# 000_Power_and_Loads.net
KiCad netlist of a schematic drawn in Altium Designer
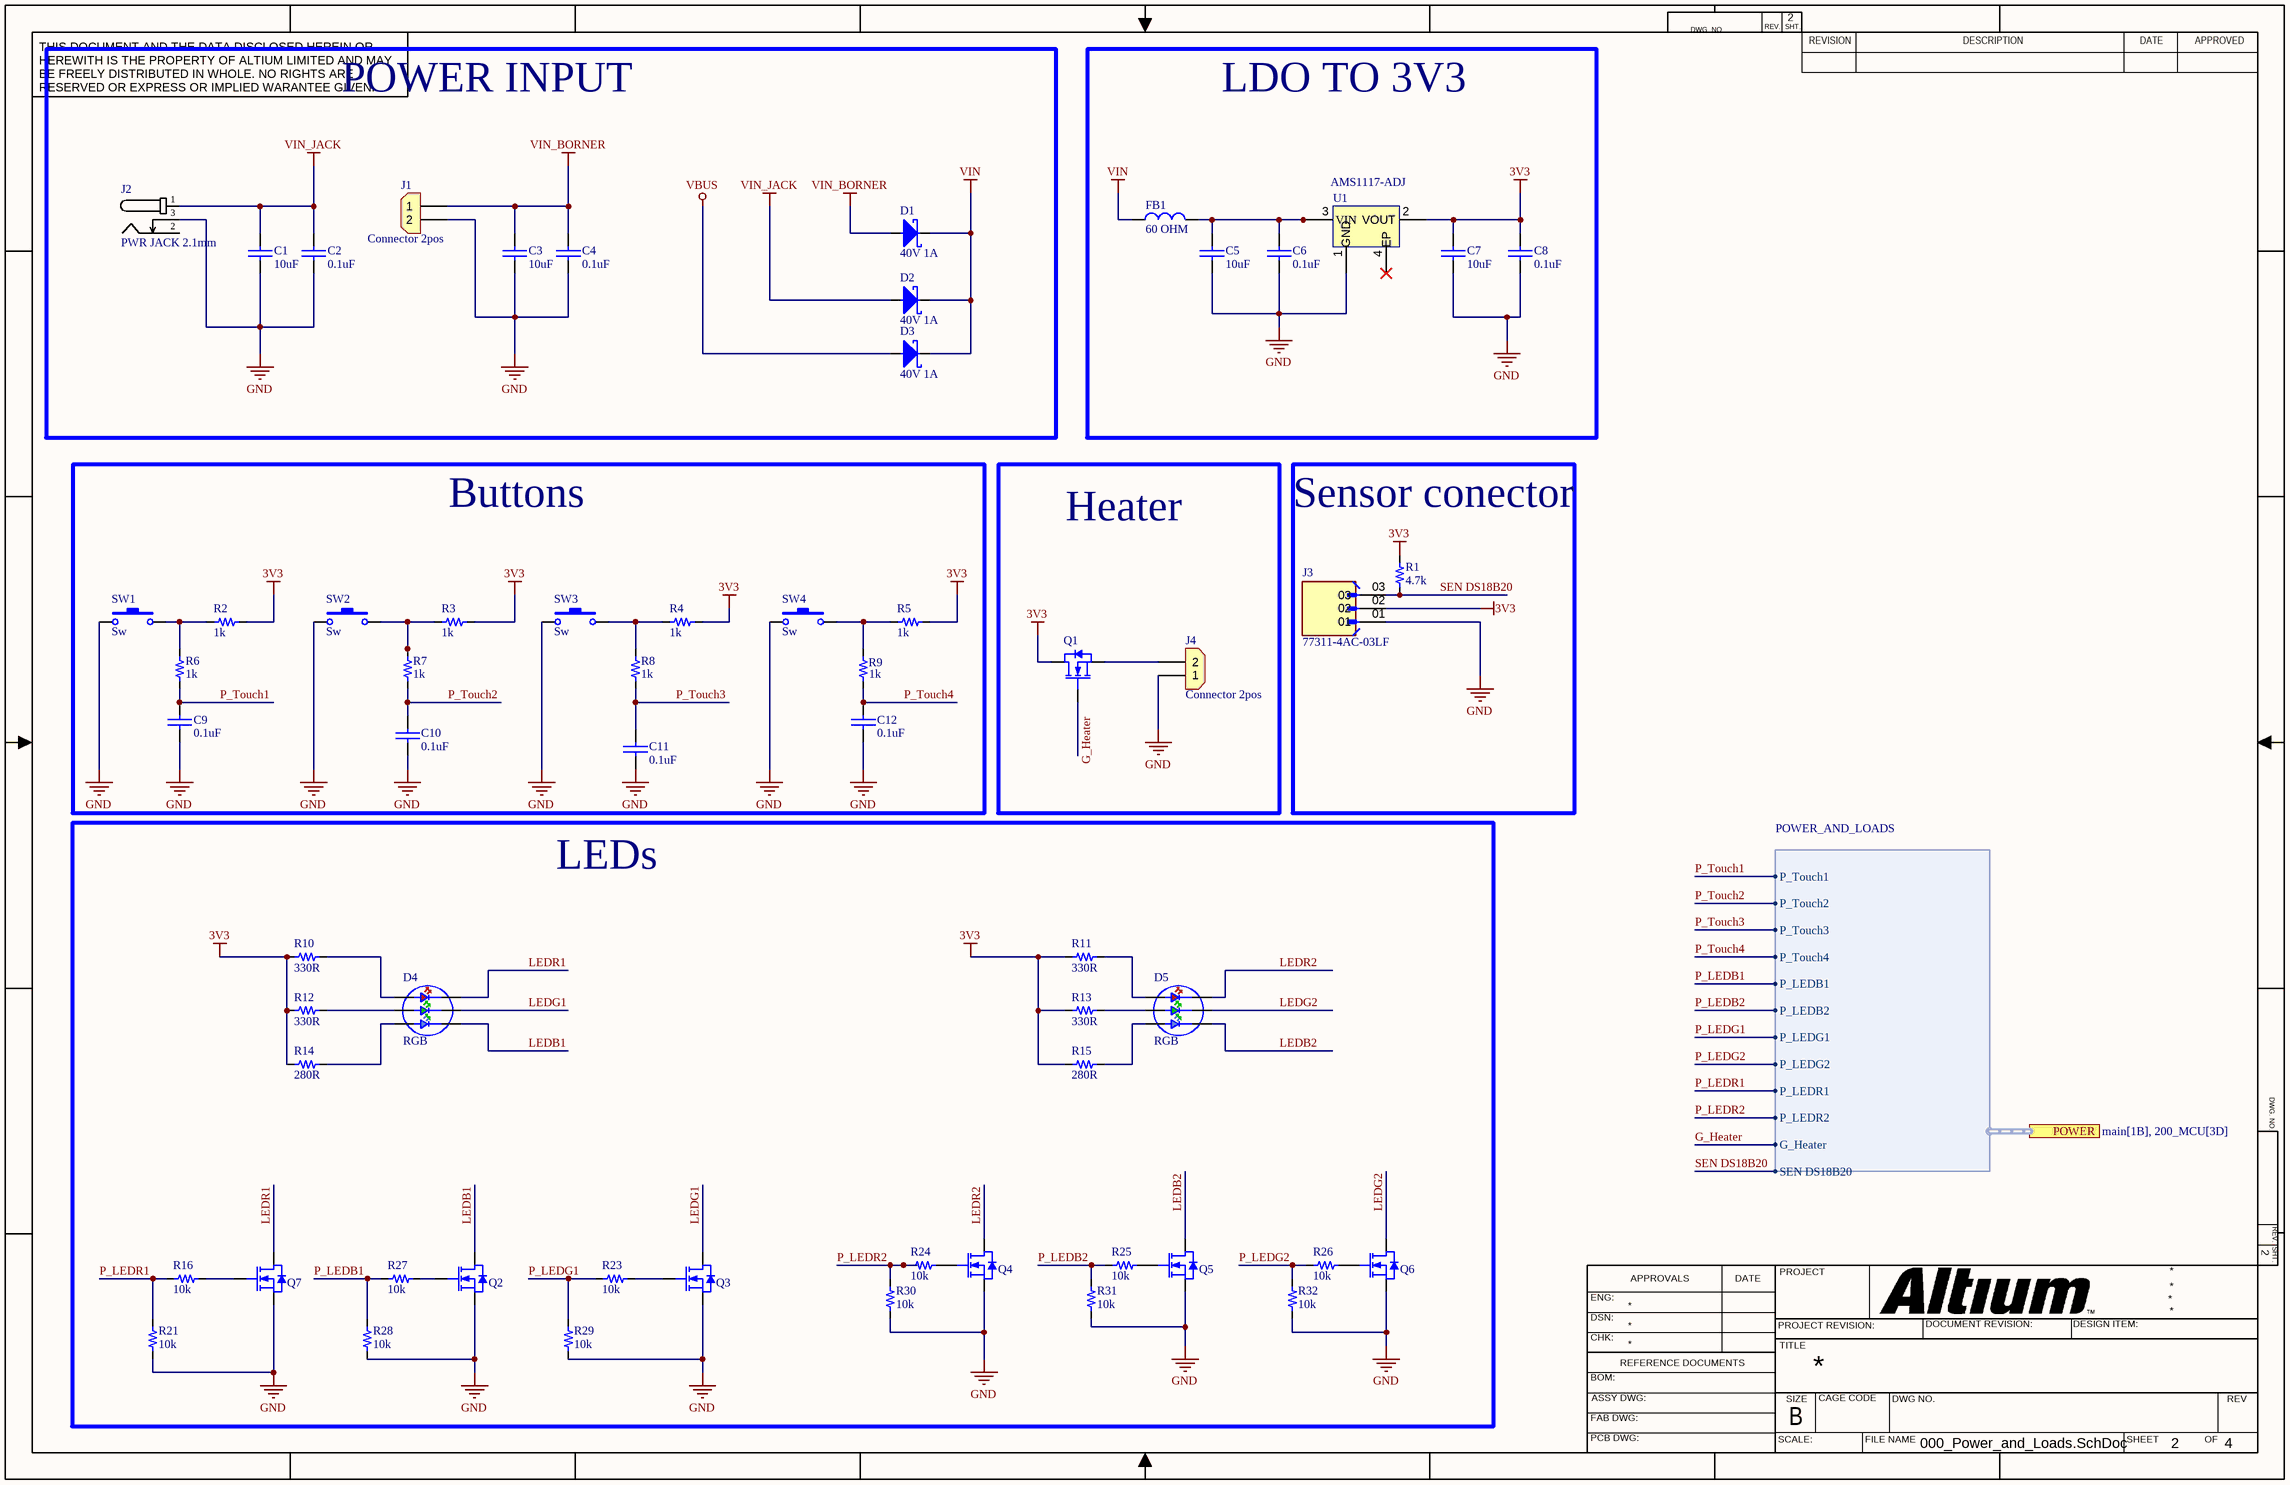
[diagram p0: 000_Power_and_Loads.SchDoc]

(export (version "E")
  (design (tool "Eeschema 10.0.6"))
  (components
    (comp (ref "C1")
      (value "10uF")
      (footprint "0603_cap")
      (description "10V 10uF X5R ±10% 0603 Multilayer Ceramic Capacitors MLCC - SMD/SMT ROHS")
      (fields
        (field (name "MANUFACTURER") "CCTC")
        (field (name "MANUFACTURER PART NUMBER") "TCC0603X5R106K100CT")
      )
      (libsource (lib "shared_lib") (part "Cap_10uF_0603_10V"))
    )
    (comp (ref "C2")
      (value "0.1uF")
      (footprint "0603_cap")
      (description "50V 100nF Y5V -20%~+80% 0603 Multilayer Ceramic Capacitors MLCC - SMD/SMT ROHS")
      (fields
        (field (name "MANUFACTURER") "Walsin Tech Corp")
        (field (name "MANUFACTURER PART NUMBER") "0603F104Z500CT")
      )
      (libsource (lib "shared_lib") (part "Cap_0.1uF_0603_50V"))
    )
    (comp (ref "C3")
      (value "10uF")
      (footprint "0603_cap")
      (description "10V 10uF X5R ±10% 0603 Multilayer Ceramic Capacitors MLCC - SMD/SMT ROHS")
      (fields
        (field (name "MANUFACTURER") "CCTC")
        (field (name "MANUFACTURER PART NUMBER") "TCC0603X5R106K100CT")
      )
      (libsource (lib "shared_lib") (part "Cap_10uF_0603_10V"))
    )
    (comp (ref "C4")
      (value "0.1uF")
      (footprint "0603_cap")
      (description "50V 100nF Y5V -20%~+80% 0603 Multilayer Ceramic Capacitors MLCC - SMD/SMT ROHS")
      (fields
        (field (name "MANUFACTURER") "Walsin Tech Corp")
        (field (name "MANUFACTURER PART NUMBER") "0603F104Z500CT")
      )
      (libsource (lib "shared_lib") (part "Cap_0.1uF_0603_50V"))
    )
    (comp (ref "C5")
      (value "10uF")
      (footprint "0603_cap")
      (description "10V 10uF X5R ±10% 0603 Multilayer Ceramic Capacitors MLCC - SMD/SMT ROHS")
      (fields
        (field (name "MANUFACTURER") "CCTC")
        (field (name "MANUFACTURER PART NUMBER") "TCC0603X5R106K100CT")
      )
      (libsource (lib "shared_lib") (part "Cap_10uF_0603_10V"))
    )
    (comp (ref "C6")
      (value "0.1uF")
      (footprint "0603_cap")
      (description "50V 100nF Y5V -20%~+80% 0603 Multilayer Ceramic Capacitors MLCC - SMD/SMT ROHS")
      (fields
        (field (name "MANUFACTURER") "Walsin Tech Corp")
        (field (name "MANUFACTURER PART NUMBER") "0603F104Z500CT")
      )
      (libsource (lib "shared_lib") (part "Cap_0.1uF_0603_50V"))
    )
    (comp (ref "C7")
      (value "10uF")
      (footprint "0603_cap")
      (description "10V 10uF X5R ±10% 0603 Multilayer Ceramic Capacitors MLCC - SMD/SMT ROHS")
      (fields
        (field (name "MANUFACTURER") "CCTC")
        (field (name "MANUFACTURER PART NUMBER") "TCC0603X5R106K100CT")
      )
      (libsource (lib "shared_lib") (part "Cap_10uF_0603_10V"))
    )
    (comp (ref "C8")
      (value "0.1uF")
      (footprint "0603_cap")
      (description "50V 100nF Y5V -20%~+80% 0603 Multilayer Ceramic Capacitors MLCC - SMD/SMT ROHS")
      (fields
        (field (name "MANUFACTURER") "Walsin Tech Corp")
        (field (name "MANUFACTURER PART NUMBER") "0603F104Z500CT")
      )
      (libsource (lib "shared_lib") (part "Cap_0.1uF_0603_50V"))
    )
    (comp (ref "C9")
      (value "0.1uF")
      (footprint "0603_cap")
      (description "50V 100nF Y5V -20%~+80% 0603 Multilayer Ceramic Capacitors MLCC - SMD/SMT ROHS")
      (fields
        (field (name "MANUFACTURER") "Walsin Tech Corp")
        (field (name "MANUFACTURER PART NUMBER") "0603F104Z500CT")
      )
      (libsource (lib "shared_lib") (part "Cap_0.1uF_0603_50V"))
    )
    (comp (ref "C10")
      (value "0.1uF")
      (footprint "0603_cap")
      (description "50V 100nF Y5V -20%~+80% 0603 Multilayer Ceramic Capacitors MLCC - SMD/SMT ROHS")
      (fields
        (field (name "MANUFACTURER") "Walsin Tech Corp")
        (field (name "MANUFACTURER PART NUMBER") "0603F104Z500CT")
      )
      (libsource (lib "shared_lib") (part "Cap_0.1uF_0603_50V"))
    )
    (comp (ref "C11")
      (value "0.1uF")
      (footprint "0603_cap")
      (description "50V 100nF Y5V -20%~+80% 0603 Multilayer Ceramic Capacitors MLCC - SMD/SMT ROHS")
      (fields
        (field (name "MANUFACTURER") "Walsin Tech Corp")
        (field (name "MANUFACTURER PART NUMBER") "0603F104Z500CT")
      )
      (libsource (lib "shared_lib") (part "Cap_0.1uF_0603_50V"))
    )
    (comp (ref "C12")
      (value "0.1uF")
      (footprint "0603_cap")
      (description "50V 100nF Y5V -20%~+80% 0603 Multilayer Ceramic Capacitors MLCC - SMD/SMT ROHS")
      (fields
        (field (name "MANUFACTURER") "Walsin Tech Corp")
        (field (name "MANUFACTURER PART NUMBER") "0603F104Z500CT")
      )
      (libsource (lib "shared_lib") (part "Cap_0.1uF_0603_50V"))
    )
    (comp (ref "D1")
      (value "40V 1A")
      (footprint "SOD_123")
      (description "DIODE SCHOTTKY 40V 1A SOD123F")
      (fields
        (field (name "MANUFACTURER") "Shanghai Prisemi Elec")
        (field (name "MANUFACTURER PART NUMBER") "PSBD1DF40V1H")
      )
      (libsource (lib "shared_lib") (part "D_Schottky_40V_1A_SOD_123F"))
    )
    (comp (ref "D2")
      (value "40V 1A")
      (footprint "SOD_123")
      (description "DIODE SCHOTTKY 40V 1A SOD123F")
      (fields
        (field (name "MANUFACTURER") "Shanghai Prisemi Elec")
        (field (name "MANUFACTURER PART NUMBER") "PSBD1DF40V1H")
      )
      (libsource (lib "shared_lib") (part "D_Schottky_40V_1A_SOD_123F"))
    )
    (comp (ref "D3")
      (value "40V 1A")
      (footprint "SOD_123")
      (description "DIODE SCHOTTKY 40V 1A SOD123F")
      (fields
        (field (name "MANUFACTURER") "Shanghai Prisemi Elec")
        (field (name "MANUFACTURER PART NUMBER") "PSBD1DF40V1H")
      )
      (libsource (lib "shared_lib") (part "D_Schottky_40V_1A_SOD_123F"))
    )
    (comp (ref "D4")
      (value "RGB")
      (footprint "RGB_NS_3.5X3.7")
      (description "-30℃~+85℃ RGB 110° 3535(mm) Light Emitting Diodes (LED) ROHS")
      (fields
        (field (name "MANUFACTURER") "Foshan NationStar Optoelectronics")
        (field (name "MANUFACTURER PART NUMBER") "RS-3535MWAM")
      )
      (libsource (lib "shared_lib") (part "LED_RGB_3535_SMD"))
    )
    (comp (ref "D5")
      (value "RGB")
      (footprint "RGB_NS_3.5X3.7")
      (description "-30℃~+85℃ RGB 110° 3535(mm) Light Emitting Diodes (LED) ROHS")
      (fields
        (field (name "MANUFACTURER") "Foshan NationStar Optoelectronics")
        (field (name "MANUFACTURER PART NUMBER") "RS-3535MWAM")
      )
      (libsource (lib "shared_lib") (part "LED_RGB_3535_SMD"))
    )
    (comp (ref "FB1")
      (value "60 OHM")
      (footprint "0603_fb")
      (description "2A 1 100mΩ 60Ω@100MHz ±25% 0603 Ferrite Beads ROHS")
      (fields
        (field (name "MANUFACTURER") "TAI-TECH")
        (field (name "MANUFACTURER PART NUMBER") "HCB1608KF-600T20")
      )
      (libsource (lib "shared_lib") (part "FB_60_0603_2A"))
    )
    (comp (ref "J1")
      (value "Connector 2pos")
      (footprint "CON_2x1_TH_5MM")
      (description "2POS 5MM")
      (fields (field (name "MANUFACTURER") "JILN") (field (name "MANUFACTURER PART NUMBER") "JL126-50002G01"))
      (libsource (lib "shared_lib") (part "Con_2x1_TH_5mm"))
    )
    (comp (ref "J2")
      (value "PWR JACK 2.1mm")
      (footprint "CON_POWER_BARREL_2.1MM_3CONN")
      (description "CONN PWR JACK 2X5.5MM SOLDER")
      (fields (field (name "MANUFACTURER") "HCTL") (field (name "MANUFACTURER PART NUMBER") "HC-DC-005-2.0T"))
      (libsource (lib "shared_lib") (part "Con_Power_Jack_2.1mm_3pins"))
    )
    (comp (ref "J3")
      (value "77311-4AC-03LF")
      (footprint "AMPHENOL_77311-4AC-03LF")
      (description "Connector Header Through Hole 3 position 0.100\" (2.54mm)")
      (fields (field (name "MANUFACTURER") "Amphenol ICC (FCI)"))
      (libsource (lib "3pines") (part "77311-4AC-03LF"))
    )
    (comp (ref "J4")
      (value "Connector 2pos")
      (footprint "CON_2x1_TH_5MM")
      (description "2POS 5MM")
      (fields (field (name "MANUFACTURER") "JILN") (field (name "MANUFACTURER PART NUMBER") "JL126-50002G01"))
      (libsource (lib "shared_lib") (part "Con_2x1_TH_5mm"))
    )
    (comp (ref "Q1")
      (value "N CH")
      (footprint "SOT_23_3")
      (description "MOSFET N-CH 20V SOT23")
      (fields (field (name "MANUFACTURER") "Doeshare") (field (name "MANUFACTURER PART NUMBER") "DN2302S"))
      (libsource (lib "shared_lib") (part "Q_NFET_20V_3.2A_SOT23"))
    )
    (comp (ref "Q2")
      (value "N CH")
      (footprint "SOT_23_3")
      (description "MOSFET N-CH 20V SOT23")
      (fields (field (name "MANUFACTURER") "Doeshare") (field (name "MANUFACTURER PART NUMBER") "DN2302S"))
      (libsource (lib "shared_lib") (part "Q_NFET_20V_3.2A_SOT23"))
    )
    (comp (ref "Q3")
      (value "N CH")
      (footprint "SOT_23_3")
      (description "MOSFET N-CH 20V SOT23")
      (fields (field (name "MANUFACTURER") "Doeshare") (field (name "MANUFACTURER PART NUMBER") "DN2302S"))
      (libsource (lib "shared_lib") (part "Q_NFET_20V_3.2A_SOT23"))
    )
    (comp (ref "Q4")
      (value "N CH")
      (footprint "SOT_23_3")
      (description "MOSFET N-CH 20V SOT23")
      (fields (field (name "MANUFACTURER") "Doeshare") (field (name "MANUFACTURER PART NUMBER") "DN2302S"))
      (libsource (lib "shared_lib") (part "Q_NFET_20V_3.2A_SOT23"))
    )
    (comp (ref "Q5")
      (value "N CH")
      (footprint "SOT_23_3")
      (description "MOSFET N-CH 20V SOT23")
      (fields (field (name "MANUFACTURER") "Doeshare") (field (name "MANUFACTURER PART NUMBER") "DN2302S"))
      (libsource (lib "shared_lib") (part "Q_NFET_20V_3.2A_SOT23"))
    )
    (comp (ref "Q6")
      (value "N CH")
      (footprint "SOT_23_3")
      (description "MOSFET N-CH 20V SOT23")
      (fields (field (name "MANUFACTURER") "Doeshare") (field (name "MANUFACTURER PART NUMBER") "DN2302S"))
      (libsource (lib "shared_lib") (part "Q_NFET_20V_3.2A_SOT23"))
    )
    (comp (ref "Q7")
      (value "N CH")
      (footprint "SOT_23_3")
      (description "MOSFET N-CH 20V SOT23")
      (fields (field (name "MANUFACTURER") "Doeshare") (field (name "MANUFACTURER PART NUMBER") "DN2302S"))
      (libsource (lib "shared_lib") (part "Q_NFET_20V_3.2A_SOT23"))
    )
    (comp (ref "R1")
      (value "4.7k")
      (footprint "0603_res")
      (description "RES SMD 4.7k OHM 5% 1/10W 0603")
      (fields (field (name "MANUFACTURER") "FOJAN") (field (name "MANUFACTURER PART NUMBER") "FRC0603J103TS"))
      (libsource (lib "shared_lib") (part "Res_10k_0603_1/10W"))
    )
    (comp (ref "R2")
      (value "1k")
      (footprint "0603_res")
      (description "RES SMD 1k OHM 5% 1/10W 0603")
      (fields
        (field (name "MANUFACTURER") "FOJAN")
        (field (name "MANUFACTURER PART NUMBER") "FRC0603J102 TS")
      )
      (libsource (lib "shared_lib") (part "Res_1k_0603_1/10W"))
    )
    (comp (ref "R3")
      (value "1k")
      (footprint "0603_res")
      (description "RES SMD 1k OHM 5% 1/10W 0603")
      (fields
        (field (name "MANUFACTURER") "FOJAN")
        (field (name "MANUFACTURER PART NUMBER") "FRC0603J102 TS")
      )
      (libsource (lib "shared_lib") (part "Res_1k_0603_1/10W"))
    )
    (comp (ref "R4")
      (value "1k")
      (footprint "0603_res")
      (description "RES SMD 1k OHM 5% 1/10W 0603")
      (fields
        (field (name "MANUFACTURER") "FOJAN")
        (field (name "MANUFACTURER PART NUMBER") "FRC0603J102 TS")
      )
      (libsource (lib "shared_lib") (part "Res_1k_0603_1/10W"))
    )
    (comp (ref "R5")
      (value "1k")
      (footprint "0603_res")
      (description "RES SMD 1k OHM 5% 1/10W 0603")
      (fields
        (field (name "MANUFACTURER") "FOJAN")
        (field (name "MANUFACTURER PART NUMBER") "FRC0603J102 TS")
      )
      (libsource (lib "shared_lib") (part "Res_1k_0603_1/10W"))
    )
    (comp (ref "R6")
      (value "1k")
      (footprint "0603_res")
      (description "RES SMD 1k OHM 5% 1/10W 0603")
      (fields
        (field (name "MANUFACTURER") "FOJAN")
        (field (name "MANUFACTURER PART NUMBER") "FRC0603J102 TS")
      )
      (libsource (lib "shared_lib") (part "Res_1k_0603_1/10W"))
    )
    (comp (ref "R7")
      (value "1k")
      (footprint "0603_res")
      (description "RES SMD 1k OHM 5% 1/10W 0603")
      (fields
        (field (name "MANUFACTURER") "FOJAN")
        (field (name "MANUFACTURER PART NUMBER") "FRC0603J102 TS")
      )
      (libsource (lib "shared_lib") (part "Res_1k_0603_1/10W"))
    )
    (comp (ref "R8")
      (value "1k")
      (footprint "0603_res")
      (description "RES SMD 1k OHM 5% 1/10W 0603")
      (fields
        (field (name "MANUFACTURER") "FOJAN")
        (field (name "MANUFACTURER PART NUMBER") "FRC0603J102 TS")
      )
      (libsource (lib "shared_lib") (part "Res_1k_0603_1/10W"))
    )
    (comp (ref "R9")
      (value "1k")
      (footprint "0603_res")
      (description "RES SMD 1k OHM 5% 1/10W 0603")
      (fields
        (field (name "MANUFACTURER") "FOJAN")
        (field (name "MANUFACTURER PART NUMBER") "FRC0603J102 TS")
      )
      (libsource (lib "shared_lib") (part "Res_1k_0603_1/10W"))
    )
    (comp (ref "R10")
      (value "330R")
      (footprint "0603_res")
      (description "RES SMD 330R OHM 5% 1/10W 0603")
      (fields
        (field (name "MANUFACTURER") "FOJAN")
        (field (name "MANUFACTURER PART NUMBER") "FRC0603J331 TS")
      )
      (libsource (lib "shared_lib") (part "Res_330R_0603_1/10W"))
    )
    (comp (ref "R11")
      (value "330R")
      (footprint "0603_res")
      (description "RES SMD 330R OHM 5% 1/10W 0603")
      (fields
        (field (name "MANUFACTURER") "FOJAN")
        (field (name "MANUFACTURER PART NUMBER") "FRC0603J331 TS")
      )
      (libsource (lib "shared_lib") (part "Res_330R_0603_1/10W"))
    )
    (comp (ref "R12")
      (value "330R")
      (footprint "0603_res")
      (description "RES SMD 330R OHM 5% 1/10W 0603")
      (fields
        (field (name "MANUFACTURER") "FOJAN")
        (field (name "MANUFACTURER PART NUMBER") "FRC0603J331 TS")
      )
      (libsource (lib "shared_lib") (part "Res_330R_0603_1/10W"))
    )
    (comp (ref "R13")
      (value "330R")
      (footprint "0603_res")
      (description "RES SMD 330R OHM 5% 1/10W 0603")
      (fields
        (field (name "MANUFACTURER") "FOJAN")
        (field (name "MANUFACTURER PART NUMBER") "FRC0603J331 TS")
      )
      (libsource (lib "shared_lib") (part "Res_330R_0603_1/10W"))
    )
    (comp (ref "R14")
      (value "280R")
      (footprint "0603_res")
      (description "RES SMD 280R OHM 5% 1/10W 0603")
      (fields
        (field (name "MANUFACTURER") "FOJAN")
        (field (name "MANUFACTURER PART NUMBER") "FRC0603J331 TS")
      )
      (libsource (lib "shared_lib") (part "Res_330R_0603_1/10W"))
    )
    (comp (ref "R15")
      (value "280R")
      (footprint "0603_res")
      (description "RES SMD 280R OHM 5% 1/10W 0603")
      (fields
        (field (name "MANUFACTURER") "FOJAN")
        (field (name "MANUFACTURER PART NUMBER") "FRC0603J331 TS")
      )
      (libsource (lib "shared_lib") (part "Res_330R_0603_1/10W"))
    )
    (comp (ref "R16")
      (value "10k")
      (footprint "0603_res")
      (description "RES SMD 10k OHM 5% 1/10W 0603")
      (fields (field (name "MANUFACTURER") "FOJAN") (field (name "MANUFACTURER PART NUMBER") "FRC0603J103TS"))
      (libsource (lib "shared_lib") (part "Res_10k_0603_1/10W"))
    )
    (comp (ref "R21")
      (value "10k")
      (footprint "0603_res")
      (description "RES SMD 10k OHM 5% 1/10W 0603")
      (fields (field (name "MANUFACTURER") "FOJAN") (field (name "MANUFACTURER PART NUMBER") "FRC0603J103TS"))
      (libsource (lib "shared_lib") (part "Res_10k_0603_1/10W"))
    )
    (comp (ref "R23")
      (value "10k")
      (footprint "0603_res")
      (description "RES SMD 10k OHM 5% 1/10W 0603")
      (fields (field (name "MANUFACTURER") "FOJAN") (field (name "MANUFACTURER PART NUMBER") "FRC0603J103TS"))
      (libsource (lib "shared_lib") (part "Res_10k_0603_1/10W"))
    )
    (comp (ref "R24")
      (value "10k")
      (footprint "0603_res")
      (description "RES SMD 10k OHM 5% 1/10W 0603")
      (fields (field (name "MANUFACTURER") "FOJAN") (field (name "MANUFACTURER PART NUMBER") "FRC0603J103TS"))
      (libsource (lib "shared_lib") (part "Res_10k_0603_1/10W"))
    )
    (comp (ref "R25")
      (value "10k")
      (footprint "0603_res")
      (description "RES SMD 10k OHM 5% 1/10W 0603")
      (fields (field (name "MANUFACTURER") "FOJAN") (field (name "MANUFACTURER PART NUMBER") "FRC0603J103TS"))
      (libsource (lib "shared_lib") (part "Res_10k_0603_1/10W"))
    )
    (comp (ref "R26")
      (value "10k")
      (footprint "0603_res")
      (description "RES SMD 10k OHM 5% 1/10W 0603")
      (fields (field (name "MANUFACTURER") "FOJAN") (field (name "MANUFACTURER PART NUMBER") "FRC0603J103TS"))
      (libsource (lib "shared_lib") (part "Res_10k_0603_1/10W"))
    )
    (comp (ref "R27")
      (value "10k")
      (footprint "0603_res")
      (description "RES SMD 10k OHM 5% 1/10W 0603")
      (fields (field (name "MANUFACTURER") "FOJAN") (field (name "MANUFACTURER PART NUMBER") "FRC0603J103TS"))
      (libsource (lib "shared_lib") (part "Res_10k_0603_1/10W"))
    )
    (comp (ref "R28")
      (value "10k")
      (footprint "0603_res")
      (description "RES SMD 10k OHM 5% 1/10W 0603")
      (fields (field (name "MANUFACTURER") "FOJAN") (field (name "MANUFACTURER PART NUMBER") "FRC0603J103TS"))
      (libsource (lib "shared_lib") (part "Res_10k_0603_1/10W"))
    )
    (comp (ref "R29")
      (value "10k")
      (footprint "0603_res")
      (description "RES SMD 10k OHM 5% 1/10W 0603")
      (fields (field (name "MANUFACTURER") "FOJAN") (field (name "MANUFACTURER PART NUMBER") "FRC0603J103TS"))
      (libsource (lib "shared_lib") (part "Res_10k_0603_1/10W"))
    )
    (comp (ref "R30")
      (value "10k")
      (footprint "0603_res")
      (description "RES SMD 10k OHM 5% 1/10W 0603")
      (fields (field (name "MANUFACTURER") "FOJAN") (field (name "MANUFACTURER PART NUMBER") "FRC0603J103TS"))
      (libsource (lib "shared_lib") (part "Res_10k_0603_1/10W"))
    )
    (comp (ref "R31")
      (value "10k")
      (footprint "0603_res")
      (description "RES SMD 10k OHM 5% 1/10W 0603")
      (fields (field (name "MANUFACTURER") "FOJAN") (field (name "MANUFACTURER PART NUMBER") "FRC0603J103TS"))
      (libsource (lib "shared_lib") (part "Res_10k_0603_1/10W"))
    )
    (comp (ref "R32")
      (value "10k")
      (footprint "0603_res")
      (description "RES SMD 10k OHM 5% 1/10W 0603")
      (fields (field (name "MANUFACTURER") "FOJAN") (field (name "MANUFACTURER PART NUMBER") "FRC0603J103TS"))
      (libsource (lib "shared_lib") (part "Res_10k_0603_1/10W"))
    )
    (comp (ref "SW1")
      (value "Sw")
      (footprint "Sw_PUSH_4.5x4.5x5mm")
      (description "SWITCH TACTILE SPST-NO 0.05A 12V")
      (fields
        (field (name "MANUFACTURER") "BZCN")
        (field (name "MANUFACTURER PART NUMBER") "TSC015A05026A")
        (field (name "LAST MODIFIED BY") "N-A.Potosi")
      )
      (libsource (lib "shared_lib") (part "Sw_PUSH_4.5x4.5x5.0xmm"))
    )
    (comp (ref "SW2")
      (value "Sw")
      (footprint "Sw_PUSH_4.5x4.5x5mm")
      (description "SWITCH TACTILE SPST-NO 0.05A 12V")
      (fields
        (field (name "MANUFACTURER") "BZCN")
        (field (name "MANUFACTURER PART NUMBER") "TSC015A05026A")
        (field (name "LAST MODIFIED BY") "N-A.Potosi")
      )
      (libsource (lib "shared_lib") (part "Sw_PUSH_4.5x4.5x5.0xmm"))
    )
    (comp (ref "SW3")
      (value "Sw")
      (footprint "Sw_PUSH_4.5x4.5x5mm")
      (description "SWITCH TACTILE SPST-NO 0.05A 12V")
      (fields
        (field (name "MANUFACTURER") "BZCN")
        (field (name "MANUFACTURER PART NUMBER") "TSC015A05026A")
        (field (name "LAST MODIFIED BY") "N-A.Potosi")
      )
      (libsource (lib "shared_lib") (part "Sw_PUSH_4.5x4.5x5.0xmm"))
    )
    (comp (ref "SW4")
      (value "Sw")
      (footprint "Sw_PUSH_4.5x4.5x5mm")
      (description "SWITCH TACTILE SPST-NO 0.05A 12V")
      (fields
        (field (name "MANUFACTURER") "BZCN")
        (field (name "MANUFACTURER PART NUMBER") "TSC015A05026A")
        (field (name "LAST MODIFIED BY") "N-A.Potosi")
      )
      (libsource (lib "shared_lib") (part "Sw_PUSH_4.5x4.5x5.0xmm"))
    )
    (comp (ref "U1")
      (value "AMS1117-ADJ")
      (footprint "SOT_223")
      (fields (field (name "MANUFACTURER") "WPMtek(Wei Pan Microelectronics)"))
      (libsource (lib "shared_lib") (part "LDO_3V3_1A"))
    )
  )
  (nets
    (net (code "2") (name "/G_Heater") (class "Default")
      (node (ref "Q1") (pin "1") (pinfunction "G_1") (pintype "passive"))
    )
    (net (code "3") (name "/LEDB1") (class "Default")
      (node (ref "D4") (pin "1") (pinfunction "1_1") (pintype "passive"))
      (node (ref "Q2") (pin "3") (pinfunction "D_3") (pintype "passive"))
    )
    (net (code "4") (name "/LEDB2") (class "Default")
      (node (ref "D5") (pin "1") (pinfunction "1_1") (pintype "passive"))
      (node (ref "Q5") (pin "3") (pinfunction "D_3") (pintype "passive"))
    )
    (net (code "5") (name "/LEDG1") (class "Default")
      (node (ref "D4") (pin "2") (pinfunction "2_2") (pintype "passive"))
      (node (ref "Q3") (pin "3") (pinfunction "D_3") (pintype "passive"))
    )
    (net (code "6") (name "/LEDG2") (class "Default")
      (node (ref "D5") (pin "2") (pinfunction "2_2") (pintype "passive"))
      (node (ref "Q6") (pin "3") (pinfunction "D_3") (pintype "passive"))
    )
    (net (code "7") (name "/LEDR1") (class "Default")
      (node (ref "D4") (pin "3") (pinfunction "3_3") (pintype "passive"))
      (node (ref "Q7") (pin "3") (pinfunction "D_3") (pintype "passive"))
    )
    (net (code "8") (name "/LEDR2") (class "Default")
      (node (ref "D5") (pin "3") (pinfunction "3_3") (pintype "passive"))
      (node (ref "Q4") (pin "3") (pinfunction "D_3") (pintype "passive"))
    )
    (net (code "9") (name "/P_LEDB1") (class "Default")
      (node (ref "R27") (pin "2") (pinfunction "2_2") (pintype "passive"))
      (node (ref "R28") (pin "2") (pinfunction "2_2") (pintype "passive"))
    )
    (net (code "10") (name "/P_LEDB2") (class "Default")
      (node (ref "R25") (pin "2") (pinfunction "2_2") (pintype "passive"))
      (node (ref "R31") (pin "2") (pinfunction "2_2") (pintype "passive"))
    )
    (net (code "11") (name "/P_LEDG1") (class "Default")
      (node (ref "R23") (pin "2") (pinfunction "2_2") (pintype "passive"))
      (node (ref "R29") (pin "2") (pinfunction "2_2") (pintype "passive"))
    )
    (net (code "12") (name "/P_LEDG2") (class "Default")
      (node (ref "R26") (pin "2") (pinfunction "2_2") (pintype "passive"))
      (node (ref "R32") (pin "2") (pinfunction "2_2") (pintype "passive"))
    )
    (net (code "13") (name "/P_LEDR1") (class "Default")
      (node (ref "R16") (pin "2") (pinfunction "2_2") (pintype "passive"))
      (node (ref "R21") (pin "2") (pinfunction "2_2") (pintype "passive"))
    )
    (net (code "14") (name "/P_LEDR2") (class "Default")
      (node (ref "R24") (pin "2") (pinfunction "2_2") (pintype "passive"))
      (node (ref "R30") (pin "2") (pinfunction "2_2") (pintype "passive"))
    )
    (net (code "15") (name "/P_Touch1") (class "Default")
      (node (ref "C9") (pin "1") (pinfunction "1_1") (pintype "passive"))
      (node (ref "R6") (pin "1") (pinfunction "1_1") (pintype "passive"))
    )
    (net (code "16") (name "/P_Touch2") (class "Default")
      (node (ref "C10") (pin "1") (pinfunction "1_1") (pintype "passive"))
      (node (ref "R7") (pin "1") (pinfunction "1_1") (pintype "passive"))
    )
    (net (code "17") (name "/P_Touch3") (class "Default")
      (node (ref "C11") (pin "1") (pinfunction "1_1") (pintype "passive"))
      (node (ref "R8") (pin "1") (pinfunction "1_1") (pintype "passive"))
    )
    (net (code "18") (name "/P_Touch4") (class "Default")
      (node (ref "C12") (pin "1") (pinfunction "1_1") (pintype "passive"))
      (node (ref "R9") (pin "1") (pinfunction "1_1") (pintype "passive"))
    )
    (net (code "19") (name "/SEN DS18B20") (class "Default")
      (node (ref "J3") (pin "03") (pinfunction "03_03") (pintype "passive"))
      (node (ref "R1") (pin "2") (pinfunction "2_2") (pintype "passive"))
    )
    (net (code "21") (name "3V3") (class "Default")
      (node (ref "C7") (pin "1") (pinfunction "1_1") (pintype "passive"))
      (node (ref "C8") (pin "1") (pinfunction "1_1") (pintype "passive"))
      (node (ref "J3") (pin "02") (pinfunction "02_02") (pintype "passive"))
      (node (ref "Q1") (pin "3") (pinfunction "D_3") (pintype "passive"))
      (node (ref "R1") (pin "1") (pinfunction "1_1") (pintype "passive"))
      (node (ref "R10") (pin "1") (pinfunction "1_1") (pintype "passive"))
      (node (ref "R11") (pin "1") (pinfunction "1_1") (pintype "passive"))
      (node (ref "R12") (pin "1") (pinfunction "1_1") (pintype "passive"))
      (node (ref "R13") (pin "1") (pinfunction "1_1") (pintype "passive"))
      (node (ref "R14") (pin "1") (pinfunction "1_1") (pintype "passive"))
      (node (ref "R15") (pin "1") (pinfunction "1_1") (pintype "passive"))
      (node (ref "R2") (pin "2") (pinfunction "2_2") (pintype "passive"))
      (node (ref "R3") (pin "2") (pinfunction "2_2") (pintype "passive"))
      (node (ref "R4") (pin "2") (pinfunction "2_2") (pintype "passive"))
      (node (ref "R5") (pin "2") (pinfunction "2_2") (pintype "passive"))
      (node (ref "U1") (pin "2") (pinfunction "VOUT_2") (pintype "passive"))
    )
    (net (code "22") (name "GND") (class "Default")
      (node (ref "C1") (pin "2") (pinfunction "2_2") (pintype "passive"))
      (node (ref "C10") (pin "2") (pinfunction "2_2") (pintype "passive"))
      (node (ref "C11") (pin "2") (pinfunction "2_2") (pintype "passive"))
      (node (ref "C12") (pin "2") (pinfunction "2_2") (pintype "passive"))
      (node (ref "C2") (pin "2") (pinfunction "2_2") (pintype "passive"))
      (node (ref "C3") (pin "2") (pinfunction "2_2") (pintype "passive"))
      (node (ref "C4") (pin "2") (pinfunction "2_2") (pintype "passive"))
      (node (ref "C5") (pin "2") (pinfunction "2_2") (pintype "passive"))
      (node (ref "C6") (pin "2") (pinfunction "2_2") (pintype "passive"))
      (node (ref "C7") (pin "2") (pinfunction "2_2") (pintype "passive"))
      (node (ref "C8") (pin "2") (pinfunction "2_2") (pintype "passive"))
      (node (ref "C9") (pin "2") (pinfunction "2_2") (pintype "passive"))
      (node (ref "J1") (pin "2") (pinfunction "2_2") (pintype "passive"))
      (node (ref "J2") (pin "3") (pinfunction "3_3") (pintype "passive"))
      (node (ref "J3") (pin "01") (pinfunction "01_01") (pintype "passive"))
      (node (ref "J4") (pin "1") (pinfunction "1_1") (pintype "passive"))
      (node (ref "Q2") (pin "2") (pinfunction "S_2") (pintype "passive"))
      (node (ref "Q3") (pin "2") (pinfunction "S_2") (pintype "passive"))
      (node (ref "Q4") (pin "2") (pinfunction "S_2") (pintype "passive"))
      (node (ref "Q5") (pin "2") (pinfunction "S_2") (pintype "passive"))
      (node (ref "Q6") (pin "2") (pinfunction "S_2") (pintype "passive"))
      (node (ref "Q7") (pin "2") (pinfunction "S_2") (pintype "passive"))
      (node (ref "R21") (pin "1") (pinfunction "1_1") (pintype "passive"))
      (node (ref "R28") (pin "1") (pinfunction "1_1") (pintype "passive"))
      (node (ref "R29") (pin "1") (pinfunction "1_1") (pintype "passive"))
      (node (ref "R30") (pin "1") (pinfunction "1_1") (pintype "passive"))
      (node (ref "R31") (pin "1") (pinfunction "1_1") (pintype "passive"))
      (node (ref "R32") (pin "1") (pinfunction "1_1") (pintype "passive"))
      (node (ref "SW1") (pin "1") (pinfunction "1_1") (pintype "passive"))
      (node (ref "SW2") (pin "1") (pinfunction "1_1") (pintype "passive"))
      (node (ref "SW3") (pin "1") (pinfunction "1_1") (pintype "passive"))
      (node (ref "SW4") (pin "1") (pinfunction "1_1") (pintype "passive"))
      (node (ref "U1") (pin "1") (pinfunction "GND_1") (pintype "passive"))
    )
    (net (code "23") (name "Net-(D4-Pad4)") (class "Default")
      (node (ref "D4") (pin "4") (pinfunction "4_4") (pintype "passive"))
      (node (ref "R10") (pin "2") (pinfunction "2_2") (pintype "passive"))
    )
    (net (code "24") (name "Net-(D4-Pad5)") (class "Default")
      (node (ref "D4") (pin "5") (pinfunction "5_5") (pintype "passive"))
      (node (ref "R12") (pin "2") (pinfunction "2_2") (pintype "passive"))
    )
    (net (code "25") (name "Net-(D4-Pad6)") (class "Default")
      (node (ref "D4") (pin "6") (pinfunction "6_6") (pintype "passive"))
      (node (ref "R14") (pin "2") (pinfunction "2_2") (pintype "passive"))
    )
    (net (code "26") (name "Net-(D5-Pad4)") (class "Default")
      (node (ref "D5") (pin "4") (pinfunction "4_4") (pintype "passive"))
      (node (ref "R11") (pin "2") (pinfunction "2_2") (pintype "passive"))
    )
    (net (code "27") (name "Net-(D5-Pad5)") (class "Default")
      (node (ref "D5") (pin "5") (pinfunction "5_5") (pintype "passive"))
      (node (ref "R13") (pin "2") (pinfunction "2_2") (pintype "passive"))
    )
    (net (code "28") (name "Net-(D5-Pad6)") (class "Default")
      (node (ref "D5") (pin "6") (pinfunction "6_6") (pintype "passive"))
      (node (ref "R15") (pin "2") (pinfunction "2_2") (pintype "passive"))
    )
    (net (code "29") (name "Net-(Q1-S)") (class "Default")
      (node (ref "J4") (pin "2") (pinfunction "2_2") (pintype "passive"))
      (node (ref "Q1") (pin "2") (pinfunction "S_2") (pintype "passive"))
    )
    (net (code "30") (name "Net-(Q2-G)") (class "Default")
      (node (ref "Q2") (pin "1") (pinfunction "G_1") (pintype "passive"))
      (node (ref "R27") (pin "1") (pinfunction "1_1") (pintype "passive"))
    )
    (net (code "31") (name "Net-(Q3-G)") (class "Default")
      (node (ref "Q3") (pin "1") (pinfunction "G_1") (pintype "passive"))
      (node (ref "R23") (pin "1") (pinfunction "1_1") (pintype "passive"))
    )
    (net (code "32") (name "Net-(Q4-G)") (class "Default")
      (node (ref "Q4") (pin "1") (pinfunction "G_1") (pintype "passive"))
      (node (ref "R24") (pin "1") (pinfunction "1_1") (pintype "passive"))
    )
    (net (code "33") (name "Net-(Q5-G)") (class "Default")
      (node (ref "Q5") (pin "1") (pinfunction "G_1") (pintype "passive"))
      (node (ref "R25") (pin "1") (pinfunction "1_1") (pintype "passive"))
    )
    (net (code "34") (name "Net-(Q6-G)") (class "Default")
      (node (ref "Q6") (pin "1") (pinfunction "G_1") (pintype "passive"))
      (node (ref "R26") (pin "1") (pinfunction "1_1") (pintype "passive"))
    )
    (net (code "35") (name "Net-(Q7-G)") (class "Default")
      (node (ref "Q7") (pin "1") (pinfunction "G_1") (pintype "passive"))
      (node (ref "R16") (pin "1") (pinfunction "1_1") (pintype "passive"))
    )
    (net (code "36") (name "Net-(R2-Pad1)") (class "Default")
      (node (ref "R2") (pin "1") (pinfunction "1_1") (pintype "passive"))
      (node (ref "R6") (pin "2") (pinfunction "2_2") (pintype "passive"))
      (node (ref "SW1") (pin "2") (pinfunction "2_2") (pintype "passive"))
    )
    (net (code "37") (name "Net-(R3-Pad1)") (class "Default")
      (node (ref "R3") (pin "1") (pinfunction "1_1") (pintype "passive"))
      (node (ref "R7") (pin "2") (pinfunction "2_2") (pintype "passive"))
      (node (ref "SW2") (pin "2") (pinfunction "2_2") (pintype "passive"))
    )
    (net (code "38") (name "Net-(R4-Pad1)") (class "Default")
      (node (ref "R4") (pin "1") (pinfunction "1_1") (pintype "passive"))
      (node (ref "R8") (pin "2") (pinfunction "2_2") (pintype "passive"))
      (node (ref "SW3") (pin "2") (pinfunction "2_2") (pintype "passive"))
    )
    (net (code "39") (name "Net-(R5-Pad1)") (class "Default")
      (node (ref "R5") (pin "1") (pinfunction "1_1") (pintype "passive"))
      (node (ref "R9") (pin "2") (pinfunction "2_2") (pintype "passive"))
      (node (ref "SW4") (pin "2") (pinfunction "2_2") (pintype "passive"))
    )
    (net (code "40") (name "Net-(U1-VIN)") (class "Default")
      (node (ref "C5") (pin "1") (pinfunction "1_1") (pintype "passive"))
      (node (ref "C6") (pin "1") (pinfunction "1_1") (pintype "passive"))
      (node (ref "FB1") (pin "2") (pinfunction "2_2") (pintype "passive"))
      (node (ref "U1") (pin "3") (pinfunction "VIN_3") (pintype "passive"))
    )
    (net (code "41") (name "VBUS") (class "Default")
      (node (ref "D3") (pin "2") (pinfunction "2_2") (pintype "passive"))
    )
    (net (code "42") (name "VIN") (class "Default")
      (node (ref "D1") (pin "1") (pinfunction "1_1") (pintype "passive"))
      (node (ref "D2") (pin "1") (pinfunction "1_1") (pintype "passive"))
      (node (ref "D3") (pin "1") (pinfunction "1_1") (pintype "passive"))
      (node (ref "FB1") (pin "1") (pinfunction "1_1") (pintype "passive"))
    )
    (net (code "43") (name "VIN_BORNER") (class "Default")
      (node (ref "C3") (pin "1") (pinfunction "1_1") (pintype "passive"))
      (node (ref "C4") (pin "1") (pinfunction "1_1") (pintype "passive"))
      (node (ref "D1") (pin "2") (pinfunction "2_2") (pintype "passive"))
      (node (ref "J1") (pin "1") (pinfunction "1_1") (pintype "passive"))
    )
    (net (code "44") (name "VIN_JACK") (class "Default")
      (node (ref "C1") (pin "1") (pinfunction "1_1") (pintype "passive"))
      (node (ref "C2") (pin "1") (pinfunction "1_1") (pintype "passive"))
      (node (ref "D2") (pin "2") (pinfunction "2_2") (pintype "passive"))
      (node (ref "J2") (pin "1") (pinfunction "1_1") (pintype "passive"))
    )
    (net (code "45") (name "unconnected-(J2-Pad2)") (class "Default")
      (node (ref "J2") (pin "2") (pinfunction "2_2") (pintype "passive"))
    )
    (net (code "46") (name "unconnected-(U1-EP-Pad4)") (class "Default")
      (node (ref "U1") (pin "4") (pinfunction "EP_4") (pintype "passive+no_connect"))
    )
  )
)
